# CurlingStoneSchematic.net
KiCad netlist of a schematic drawn in Altium Designer
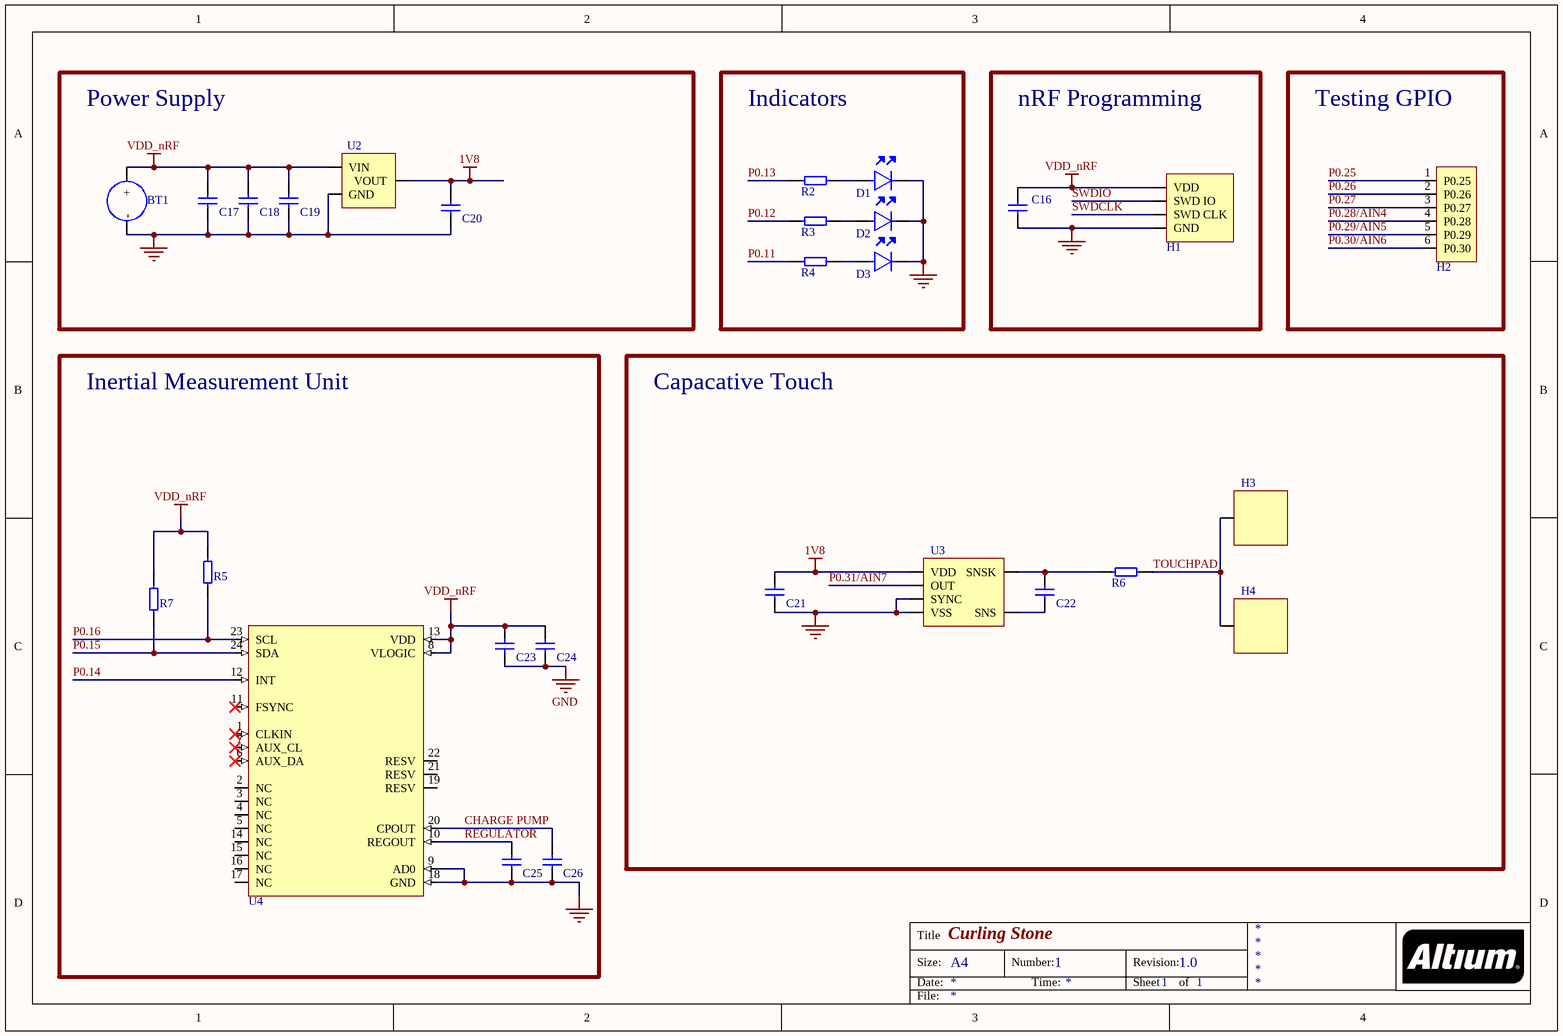
[diagram p0: CurlingStoneSchematic.SchDoc]

(export (version "E")
  (design (tool "Eeschema 10.0.6"))
  (components
    (comp (ref "BT1")
      (value "Battery Holder")
      (footprint "Battery Holder")
      (description "Battery Holder 1-Cell 20mm Size Tin Nickel SMT Mount T/R")
      (libsource (lib "CurlingStoneSchematicLibrary") (part "Battery Holder"))
    )
    (comp (ref "C16")
      (value "0603 Capacitor")
      (footprint "0603")
      (libsource (lib "CurlingStoneSchematicLibrary") (part "0603 Capacitor"))
    )
    (comp (ref "C17")
      (value "0603 Capacitor")
      (footprint "0603")
      (libsource (lib "CurlingStoneSchematicLibrary") (part "0603 Capacitor"))
    )
    (comp (ref "C18")
      (value "0603 Capacitor")
      (footprint "0603")
      (libsource (lib "CurlingStoneSchematicLibrary") (part "0603 Capacitor"))
    )
    (comp (ref "C19")
      (value "0603 Capacitor")
      (footprint "0603")
      (libsource (lib "CurlingStoneSchematicLibrary") (part "0603 Capacitor"))
    )
    (comp (ref "C20")
      (value "0603 Capacitor")
      (footprint "0603")
      (libsource (lib "CurlingStoneSchematicLibrary") (part "0603 Capacitor"))
    )
    (comp (ref "C21")
      (value "0603 Capacitor")
      (footprint "0603")
      (libsource (lib "CurlingStoneSchematicLibrary") (part "0603 Capacitor"))
    )
    (comp (ref "C22")
      (value "0603 Capacitor")
      (footprint "0603")
      (libsource (lib "CurlingStoneSchematicLibrary") (part "0603 Capacitor"))
    )
    (comp (ref "C23")
      (value "0603 Capacitor")
      (footprint "0603")
      (libsource (lib "CurlingStoneSchematicLibrary") (part "0603 Capacitor"))
    )
    (comp (ref "C24")
      (value "0603 Capacitor")
      (footprint "0603")
      (libsource (lib "CurlingStoneSchematicLibrary") (part "0603 Capacitor"))
    )
    (comp (ref "C25")
      (value "0603 Capacitor")
      (footprint "0603")
      (libsource (lib "CurlingStoneSchematicLibrary") (part "0603 Capacitor"))
    )
    (comp (ref "C26")
      (value "0603 Capacitor")
      (footprint "0603")
      (libsource (lib "CurlingStoneSchematicLibrary") (part "0603 Capacitor"))
    )
    (comp (ref "D1")
      (value "0603 LED")
      (footprint "0603 LED")
      (description "LED Uni-Color Green 574nm 2-Pin Chip LED T/R")
      (libsource (lib "CurlingStoneSchematicLibrary") (part "0603 LED"))
    )
    (comp (ref "D2")
      (value "0603 LED")
      (footprint "0603 LED")
      (description "LED Uni-Color Green 574nm 2-Pin Chip LED T/R")
      (libsource (lib "CurlingStoneSchematicLibrary") (part "0603 LED"))
    )
    (comp (ref "D3")
      (value "0603 LED")
      (footprint "0603 LED")
      (description "LED Uni-Color Green 574nm 2-Pin Chip LED T/R")
      (libsource (lib "CurlingStoneSchematicLibrary") (part "0603 LED"))
    )
    (comp (ref "H1")
      (value "4x1 Header")
      (footprint "4x1 HEADER TH")
      (libsource (lib "CurlingStoneSchematicLibrary") (part "4x1 Header"))
    )
    (comp (ref "H2")
      (value "6x1 Header")
      (footprint "6x1 HEADER TH")
      (libsource (lib "CurlingStoneSchematicLibrary") (part "6x1 Header"))
    )
    (comp (ref "H3")
      (value "Electrode")
      (footprint "ELECTRODE EXTERNAL")
      (libsource (lib "CurlingStoneSchematicLibrary") (part "Electrode"))
    )
    (comp (ref "H4")
      (value "Electrode")
      (footprint "ELECTRODE INTERNAL")
      (libsource (lib "CurlingStoneSchematicLibrary") (part "Electrode"))
    )
    (comp (ref "R2")
      (value "0603 Resistor")
      (footprint "0603")
      (libsource (lib "CurlingStoneSchematicLibrary") (part "0603 Resistor"))
    )
    (comp (ref "R3")
      (value "0603 Resistor")
      (footprint "0603")
      (libsource (lib "CurlingStoneSchematicLibrary") (part "0603 Resistor"))
    )
    (comp (ref "R4")
      (value "0603 Resistor")
      (footprint "0603")
      (libsource (lib "CurlingStoneSchematicLibrary") (part "0603 Resistor"))
    )
    (comp (ref "R5")
      (value "0603 Resistor")
      (footprint "0603")
      (libsource (lib "CurlingStoneSchematicLibrary") (part "0603 Resistor"))
    )
    (comp (ref "R6")
      (value "0603 Resistor")
      (footprint "0603")
      (libsource (lib "CurlingStoneSchematicLibrary") (part "0603 Resistor"))
    )
    (comp (ref "R7")
      (value "0603 Resistor")
      (footprint "0603")
      (libsource (lib "CurlingStoneSchematicLibrary") (part "0603 Resistor"))
    )
    (comp (ref "U2")
      (value "MCP1700 1V8")
      (footprint "MCP1700 SOT-23")
      (libsource (lib "ElsysSchematicLibrary") (part "MCP1700 1V8"))
    )
    (comp (ref "U3")
      (value "Capacative Touch")
      (footprint "CAPACATIVE TOUCH")
      (description "Capacitive Touch Screen 1Keys 6-Pin SOT-23 Tape and Reel")
      (libsource (lib "CurlingStoneSchematicLibrary") (part "Capacative Touch"))
    )
    (comp (ref "U4")
      (value "MPU-6050")
      (footprint "MPU-6050")
      (description "INVENSENSE   MPU-6050   GYRO / ACCEL, 6-AXIS, I2C, QFN-24")
      (libsource (lib "CurlingStoneSchematicLibrary") (part "MPU-6050"))
    )
  )
  (nets
    (net (code "1") (name "/CHARGE PUMP") (class "Default")
      (node (ref "C26") (pin "2") (pintype "passive"))
      (node (ref "U4") (pin "20") (pinfunction "CPOUT_20") (pintype "input"))
    )
    (net (code "2") (name "/P0.11") (class "Default") (node (ref "R4") (pin "1") (pintype "passive")))
    (net (code "3") (name "/P0.12") (class "Default") (node (ref "R3") (pin "1") (pintype "passive")))
    (net (code "4") (name "/P0.13") (class "Default") (node (ref "R2") (pin "1") (pintype "passive")))
    (net (code "5") (name "/P0.14") (class "Default")
      (node (ref "U4") (pin "12") (pinfunction "INT_12") (pintype "input"))
    )
    (net (code "6") (name "/P0.15") (class "Default")
      (node (ref "R7") (pin "1") (pintype "passive"))
      (node (ref "U4") (pin "24") (pinfunction "SDA_24") (pintype "input"))
    )
    (net (code "7") (name "/P0.16") (class "Default")
      (node (ref "R5") (pin "1") (pintype "passive"))
      (node (ref "U4") (pin "23") (pinfunction "SCL_23") (pintype "input"))
    )
    (net (code "8") (name "/P0.25") (class "Default")
      (node (ref "H2") (pin "1") (pinfunction "P0.25_1") (pintype "passive"))
    )
    (net (code "9") (name "/P0.26") (class "Default")
      (node (ref "H2") (pin "2") (pinfunction "P0.26_2") (pintype "passive"))
    )
    (net (code "10") (name "/P0.27") (class "Default")
      (node (ref "H2") (pin "3") (pinfunction "P0.27_3") (pintype "passive"))
    )
    (net (code "11") (name "/P0.28{slash}AIN4") (class "Default")
      (node (ref "H2") (pin "4") (pinfunction "P0.28_4") (pintype "passive"))
    )
    (net (code "12") (name "/P0.29{slash}AIN5") (class "Default")
      (node (ref "H2") (pin "5") (pinfunction "P0.29_5") (pintype "passive"))
    )
    (net (code "13") (name "/P0.30{slash}AIN6") (class "Default")
      (node (ref "H2") (pin "6") (pinfunction "P0.30_6") (pintype "passive"))
    )
    (net (code "14") (name "/P0.31{slash}AIN7") (class "Default")
      (node (ref "U3") (pin "1") (pinfunction "OUT_1") (pintype "passive"))
    )
    (net (code "15") (name "/REGULATOR") (class "Default")
      (node (ref "C25") (pin "2") (pintype "passive"))
      (node (ref "U4") (pin "10") (pinfunction "REGOUT_10") (pintype "input"))
    )
    (net (code "16") (name "/SWDCLK") (class "Default")
      (node (ref "H1") (pin "3") (pinfunction "SWD_CLK_3") (pintype "passive"))
    )
    (net (code "17") (name "/SWDIO") (class "Default")
      (node (ref "H1") (pin "4") (pinfunction "SWD_IO_4") (pintype "passive"))
    )
    (net (code "18") (name "/TOUCHPAD") (class "Default")
      (node (ref "H3") (pin "1") (pinfunction "GND_1") (pintype "passive"))
      (node (ref "H4") (pin "1") (pinfunction "GND_1") (pintype "passive"))
      (node (ref "R6") (pin "2") (pintype "passive"))
    )
    (net (code "19") (name "1V8") (class "Default")
      (node (ref "C20") (pin "2") (pintype "passive"))
      (node (ref "C21") (pin "2") (pintype "passive"))
      (node (ref "U2") (pin "2") (pinfunction "VOUT_2") (pintype "passive"))
      (node (ref "U3") (pin "5") (pinfunction "VDD_5") (pintype "passive"))
    )
    (net (code "20") (name "GND") (class "Default")
      (node (ref "BT1") (pin "2") (pinfunction "-_2") (pintype "passive"))
      (node (ref "C16") (pin "1") (pintype "passive"))
      (node (ref "C17") (pin "1") (pintype "passive"))
      (node (ref "C18") (pin "1") (pintype "passive"))
      (node (ref "C19") (pin "1") (pintype "passive"))
      (node (ref "C20") (pin "1") (pintype "passive"))
      (node (ref "C21") (pin "1") (pintype "passive"))
      (node (ref "C23") (pin "1") (pintype "passive"))
      (node (ref "C24") (pin "1") (pintype "passive"))
      (node (ref "C25") (pin "1") (pintype "passive"))
      (node (ref "C26") (pin "1") (pintype "passive"))
      (node (ref "D1") (pin "2") (pintype "passive"))
      (node (ref "D2") (pin "2") (pintype "passive"))
      (node (ref "D3") (pin "2") (pintype "passive"))
      (node (ref "H1") (pin "2") (pinfunction "GND_2") (pintype "passive"))
      (node (ref "U2") (pin "1") (pinfunction "GND_1") (pintype "passive"))
      (node (ref "U3") (pin "2") (pinfunction "VSS_2") (pintype "passive"))
      (node (ref "U3") (pin "6") (pinfunction "SYNC_6") (pintype "passive"))
      (node (ref "U4") (pin "18") (pinfunction "GND_18") (pintype "input"))
      (node (ref "U4") (pin "9") (pinfunction "AD0_9") (pintype "input"))
    )
    (net (code "21") (name "Net-(D1-Pad1)") (class "Default")
      (node (ref "D1") (pin "1") (pintype "passive"))
      (node (ref "R2") (pin "2") (pintype "passive"))
    )
    (net (code "22") (name "Net-(D2-Pad1)") (class "Default")
      (node (ref "D2") (pin "1") (pintype "passive"))
      (node (ref "R3") (pin "2") (pintype "passive"))
    )
    (net (code "23") (name "Net-(D3-Pad1)") (class "Default")
      (node (ref "D3") (pin "1") (pintype "passive"))
      (node (ref "R4") (pin "2") (pintype "passive"))
    )
    (net (code "24") (name "Net-(U3-SNS)") (class "Default")
      (node (ref "C22") (pin "1") (pintype "passive"))
      (node (ref "U3") (pin "4") (pinfunction "SNS_4") (pintype "passive"))
    )
    (net (code "25") (name "Net-(U3-SNSK)") (class "Default")
      (node (ref "C22") (pin "2") (pintype "passive"))
      (node (ref "R6") (pin "1") (pintype "passive"))
      (node (ref "U3") (pin "3") (pinfunction "SNSK_3") (pintype "passive"))
    )
    (net (code "26") (name "VDD_nRF") (class "Default")
      (node (ref "BT1") (pin "1") (pinfunction "+_1") (pintype "passive"))
      (node (ref "C16") (pin "2") (pintype "passive"))
      (node (ref "C17") (pin "2") (pintype "passive"))
      (node (ref "C18") (pin "2") (pintype "passive"))
      (node (ref "C19") (pin "2") (pintype "passive"))
      (node (ref "C23") (pin "2") (pintype "passive"))
      (node (ref "C24") (pin "2") (pintype "passive"))
      (node (ref "H1") (pin "1") (pinfunction "VDD_1") (pintype "passive"))
      (node (ref "R5") (pin "2") (pintype "passive"))
      (node (ref "R7") (pin "2") (pintype "passive"))
      (node (ref "U2") (pin "3") (pinfunction "VIN_3") (pintype "passive"))
      (node (ref "U4") (pin "13") (pinfunction "VDD_13") (pintype "input"))
      (node (ref "U4") (pin "8") (pinfunction "VLOGIC_8") (pintype "input"))
    )
    (net (code "27") (name "unconnected-(U4-AUX_CL-Pad7)") (class "Default")
      (node (ref "U4") (pin "7") (pinfunction "AUX_CL_7") (pintype "input+no_connect"))
    )
    (net (code "28") (name "unconnected-(U4-AUX_DA-Pad6)") (class "Default")
      (node (ref "U4") (pin "6") (pinfunction "AUX_DA_6") (pintype "input+no_connect"))
    )
    (net (code "29") (name "unconnected-(U4-CLKIN-Pad1)") (class "Default")
      (node (ref "U4") (pin "1") (pinfunction "CLKIN_1") (pintype "input+no_connect"))
    )
    (net (code "30") (name "unconnected-(U4-FSYNC-Pad11)") (class "Default")
      (node (ref "U4") (pin "11") (pinfunction "FSYNC_11") (pintype "input+no_connect"))
    )
    (net (code "31") (name "unconnected-(U4-NC-Pad2)") (class "Default")
      (node (ref "U4") (pin "2") (pinfunction "NC_2") (pintype "passive"))
    )
    (net (code "32") (name "unconnected-(U4-NC-Pad3)") (class "Default")
      (node (ref "U4") (pin "3") (pinfunction "NC_3") (pintype "passive"))
    )
    (net (code "33") (name "unconnected-(U4-NC-Pad4)") (class "Default")
      (node (ref "U4") (pin "4") (pinfunction "NC_4") (pintype "passive"))
    )
    (net (code "34") (name "unconnected-(U4-NC-Pad5)") (class "Default")
      (node (ref "U4") (pin "5") (pinfunction "NC_5") (pintype "passive"))
    )
    (net (code "35") (name "unconnected-(U4-NC-Pad14)") (class "Default")
      (node (ref "U4") (pin "14") (pinfunction "NC_14") (pintype "passive"))
    )
    (net (code "36") (name "unconnected-(U4-NC-Pad15)") (class "Default")
      (node (ref "U4") (pin "15") (pinfunction "NC_15") (pintype "passive"))
    )
    (net (code "37") (name "unconnected-(U4-NC-Pad16)") (class "Default")
      (node (ref "U4") (pin "16") (pinfunction "NC_16") (pintype "passive"))
    )
    (net (code "38") (name "unconnected-(U4-NC-Pad17)") (class "Default")
      (node (ref "U4") (pin "17") (pinfunction "NC_17") (pintype "passive"))
    )
    (net (code "39") (name "unconnected-(U4-RESV-Pad19)") (class "Default")
      (node (ref "U4") (pin "19") (pinfunction "RESV_19") (pintype "passive"))
    )
    (net (code "40") (name "unconnected-(U4-RESV-Pad21)") (class "Default")
      (node (ref "U4") (pin "21") (pinfunction "RESV_21") (pintype "passive"))
    )
    (net (code "41") (name "unconnected-(U4-RESV-Pad22)") (class "Default")
      (node (ref "U4") (pin "22") (pinfunction "RESV_22") (pintype "passive"))
    )
  )
)
